# SIM800C_V1_2.net
KiCad netlist of a schematic drawn in Altium Designer
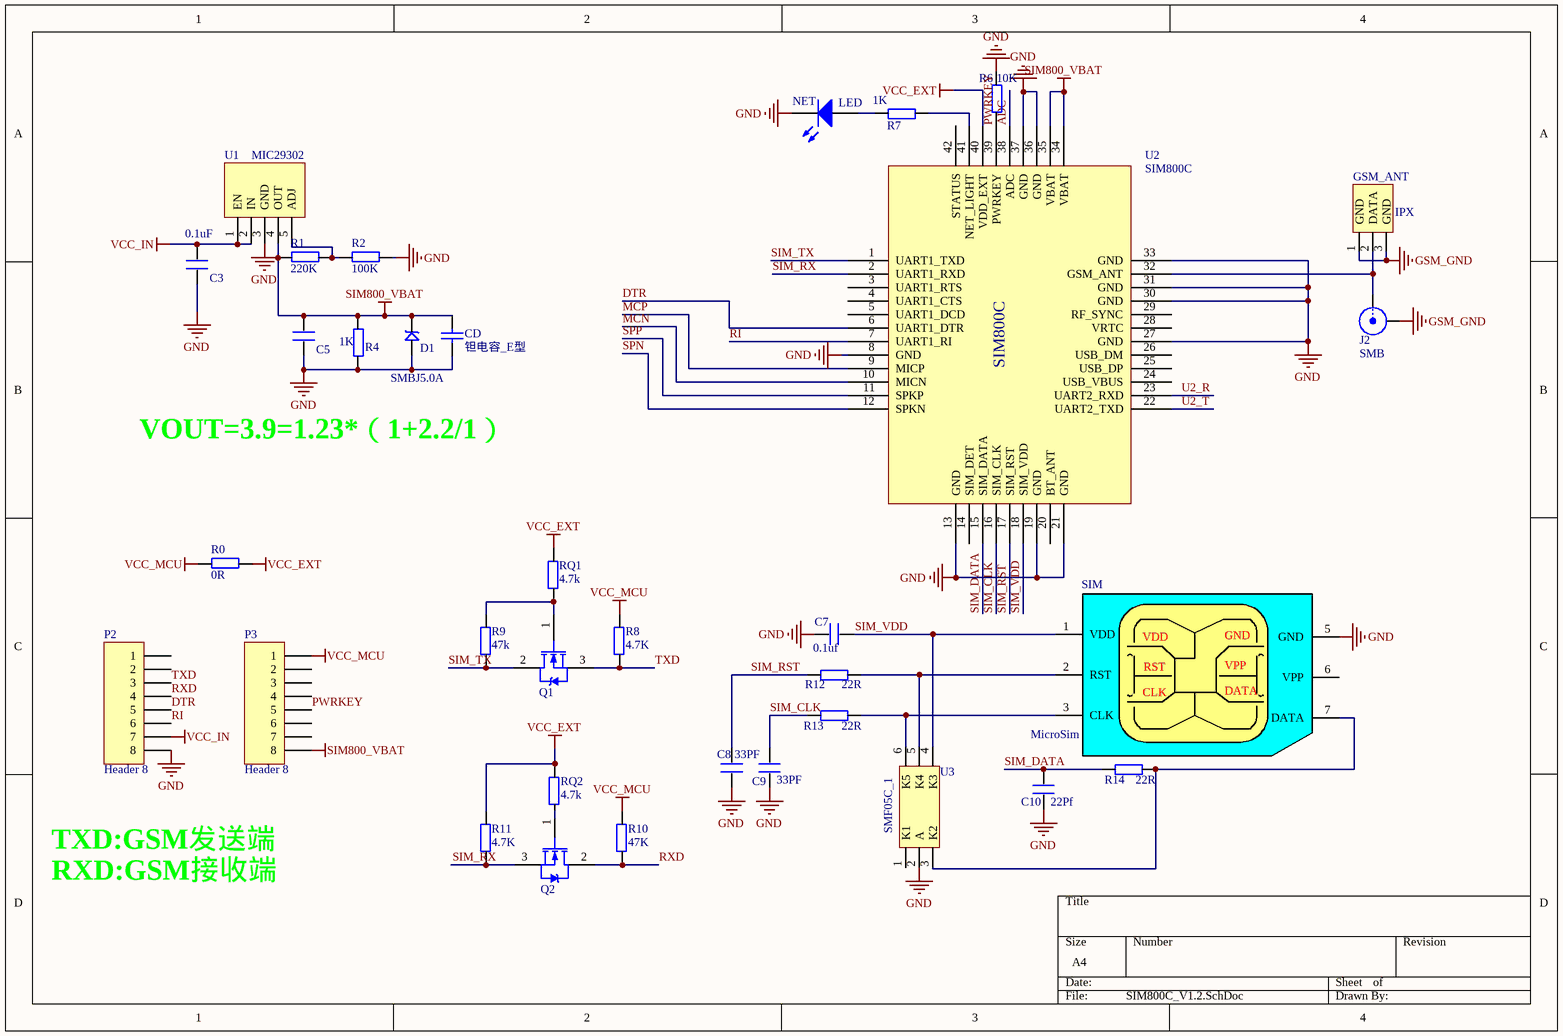
[diagram p0: SIM800C_V1.2.SchDoc]

(export (version "E")
  (design (tool "Eeschema 10.0.6"))
  (components
    (comp (ref "C3") (value "0.1uF") (footprint "0603P") (libsource (lib "SIM800C 原理图库") (part "C")))
    (comp (ref "C5") (value "0.1uF") (footprint "0603P") (libsource (lib "SIM800C 原理图库") (part "C_2")))
    (comp (ref "C7") (value "0.1uf") (footprint "0603P") (libsource (lib "SIM800C 原理图库") (part "C")))
    (comp (ref "C8")
      (value "22UF")
      (footprint "0603P")
      (fields (field (name "ALTIUM_UNNAMED_1") "33PF"))
      (libsource (lib "SIM800C 原理图库") (part "C"))
    )
    (comp (ref "C9")
      (value "22UF")
      (footprint "0603P")
      (fields (field (name "ALTIUM_UNNAMED_1") "33PF"))
      (libsource (lib "SIM800C 原理图库") (part "C"))
    )
    (comp (ref "C10") (value "22Pf") (footprint "0603P") (libsource (lib "SIM800C 原理图库") (part "C")))
    (comp (ref "CD") (value "钽电容_E型") (footprint "钽电容_E型") (libsource (lib "pvbox-lib") (part "钽电容_E型")))
    (comp (ref "D1")
      (value "SMBJ5.0A")
      (footprint "SMBJ")
      (description "TVS")
      (fields (field (name "ALTIUM_UNNAMED_1") "SMBJ5.0A"))
      (libsource (lib "SIM800C 原理图库") (part "SMBJ"))
    )
    (comp (ref "GSM_ANT")
      (value "IPX")
      (footprint "IPX")
      (description "IPEX座")
      (libsource (lib "SIM800C 原理图库") (part "IPEX"))
    )
    (comp (ref "J2")
      (value "SMB")
      (footprint "SMB_V-RJ45")
      (description "SMB Straight Connector")
      (fields (field (name "PUBLISHER") "Altium Limited"))
      (libsource (lib "SIM800C 原理图库") (part "SMB"))
    )
    (comp (ref "NET")
      (value "LED")
      (footprint "SMDLED")
      (description "Typical RED, GREEN, YELLOW, AMBER GaAs LED")
      (fields (field (name "PUBLISHER") "Altium Limited"))
      (libsource (lib "SIM800C 原理图库") (part "LED2"))
    )
    (comp (ref "P2")
      (value "Header 8")
      (footprint "HDR1X8")
      (description "Header, 8-Pin")
      (fields (field (name "PUBLISHER") "Altium Limited"))
      (libsource (lib "SIM800C 原理图库") (part "Header 8"))
    )
    (comp (ref "P3")
      (value "Header 8")
      (footprint "HDR1X8")
      (description "Header, 8-Pin")
      (fields (field (name "PUBLISHER") "Altium Limited"))
      (libsource (lib "SIM800C 原理图库") (part "Header 8"))
    )
    (comp (ref "Q1")
      (value "NMOS-2")
      (footprint "SOT-23")
      (description "N-Channel Power MOSFET")
      (fields (field (name "PUBLISHER") "Altium Limited"))
      (libsource (lib "SIM800C 原理图库") (part "NMOS-2"))
    )
    (comp (ref "Q2")
      (value "NMOS-2")
      (footprint "SOT-23")
      (description "N-Channel Power MOSFET")
      (fields (field (name "PUBLISHER") "Altium Limited"))
      (libsource (lib "SIM800C 原理图库") (part "NMOS-2"))
    )
    (comp (ref "R0") (value "0R") (footprint "0603P") (libsource (lib "SIM800C 原理图库") (part "R")))
    (comp (ref "R1") (value "220K") (footprint "0603P") (libsource (lib "SIM800C 原理图库") (part "R")))
    (comp (ref "R2") (value "100K") (footprint "0603P") (libsource (lib "SIM800C 原理图库") (part "R")))
    (comp (ref "R4") (value "1K") (footprint "0603P") (libsource (lib "SIM800C 原理图库") (part "R")))
    (comp (ref "R6") (value "10K") (footprint "CORE:0603P") (libsource (lib "SIM800C 原理图库") (part "R")))
    (comp (ref "R7") (value "1K") (footprint "CORE:0603P") (libsource (lib "SIM800C 原理图库") (part "R")))
    (comp (ref "R8") (value "4.7K") (footprint "CORE:0603P") (libsource (lib "SIM800C 原理图库") (part "R")))
    (comp (ref "R9") (value "47k") (footprint "CORE:0603P") (libsource (lib "SIM800C 原理图库") (part "R")))
    (comp (ref "R10") (value "47K") (footprint "CORE:0603P") (libsource (lib "SIM800C 原理图库") (part "R")))
    (comp (ref "R11") (value "4.7K") (footprint "CORE:0603P") (libsource (lib "SIM800C 原理图库") (part "R")))
    (comp (ref "R12") (value "22R") (footprint "CORE:0603P") (libsource (lib "SIM800C 原理图库") (part "R")))
    (comp (ref "R13") (value "22R") (footprint "CORE:0603P") (libsource (lib "SIM800C 原理图库") (part "R")))
    (comp (ref "R14") (value "22R") (footprint "CORE:0603P") (libsource (lib "SIM800C 原理图库") (part "R")))
    (comp (ref "RQ1") (value "4.7k") (footprint "CORE:0603P") (libsource (lib "SIM800C 原理图库") (part "R")))
    (comp (ref "RQ2") (value "4.7k") (footprint "CORE:0603P") (libsource (lib "SIM800C 原理图库") (part "R")))
    (comp (ref "SIM") (value "MicroSim") (footprint "SIM卡 自弹") (libsource (lib "pvbox-lib") (part "SIM卡 自弹")))
    (comp (ref "U1")
      (value "MIC29302")
      (footprint "D2PAK")
      (libsource (lib "SIM800C 原理图库") (part "MIC29302"))
    )
    (comp (ref "U2")
      (value "SIM800C")
      (footprint "SIM800C")
      (libsource (lib "SIM800C 原理图库") (part "SIM800C"))
    )
    (comp (ref "U3")
      (value "SMF05C_1")
      (footprint "SOT-363")
      (description "TVS")
      (libsource (lib "SIM800C 原理图库") (part "SMF05C_1"))
    )
  )
  (nets
    (net (code "1") (name "/ADC") (class "Default")
      (node (ref "U2") (pin "38") (pinfunction "ADC_38") (pintype "passive"))
    )
    (net (code "2") (name "/DTR") (class "Default")
      (node (ref "P2") (pin "5") (pinfunction "5_5") (pintype "passive"))
      (node (ref "U2") (pin "6") (pinfunction "UART1_DTR_6") (pintype "passive"))
    )
    (net (code "3") (name "/MCN") (class "Default")
      (node (ref "U2") (pin "10") (pinfunction "MICN_10") (pintype "passive"))
    )
    (net (code "4") (name "/MCP") (class "Default")
      (node (ref "U2") (pin "9") (pinfunction "MICP_9") (pintype "passive"))
    )
    (net (code "5") (name "/PWRKEY") (class "Default")
      (node (ref "P3") (pin "5") (pinfunction "5_5") (pintype "passive"))
      (node (ref "R6") (pin "1") (pintype "passive"))
      (node (ref "U2") (pin "39") (pinfunction "PWRKEY_39") (pintype "passive"))
    )
    (net (code "6") (name "/RI") (class "Default")
      (node (ref "P2") (pin "6") (pinfunction "6_6") (pintype "passive"))
      (node (ref "U2") (pin "7") (pinfunction "UART1_RI_7") (pintype "passive"))
    )
    (net (code "7") (name "/RXD") (class "Default")
      (node (ref "P2") (pin "4") (pinfunction "4_4") (pintype "passive"))
      (node (ref "Q2") (pin "2") (pinfunction "D_2") (pintype "passive"))
      (node (ref "R10") (pin "1") (pintype "passive"))
    )
    (net (code "8") (name "/SIM_CLK") (class "Default")
      (node (ref "C9") (pin "2") (pintype "passive"))
      (node (ref "R13") (pin "1") (pintype "passive"))
      (node (ref "U2") (pin "16") (pinfunction "SIM_CLK_16") (pintype "passive"))
    )
    (net (code "9") (name "/SIM_DATA") (class "Default")
      (node (ref "C10") (pin "2") (pintype "passive"))
      (node (ref "R14") (pin "1") (pintype "passive"))
      (node (ref "U2") (pin "15") (pinfunction "SIM_DATA_15") (pintype "passive"))
    )
    (net (code "10") (name "/SIM_RST") (class "Default")
      (node (ref "C8") (pin "2") (pintype "passive"))
      (node (ref "R12") (pin "1") (pintype "passive"))
      (node (ref "U2") (pin "17") (pinfunction "SIM_RST_17") (pintype "passive"))
    )
    (net (code "11") (name "/SIM_RX") (class "Default")
      (node (ref "Q2") (pin "3") (pinfunction "S_3") (pintype "passive"))
      (node (ref "R11") (pin "1") (pintype "passive"))
      (node (ref "U2") (pin "2") (pinfunction "UART1_RXD_2") (pintype "passive"))
    )
    (net (code "12") (name "/SIM_TX") (class "Default")
      (node (ref "Q1") (pin "2") (pinfunction "D_2") (pintype "passive"))
      (node (ref "R9") (pin "1") (pintype "passive"))
      (node (ref "U2") (pin "1") (pinfunction "UART1_TXD_1") (pintype "passive"))
    )
    (net (code "13") (name "/SIM_VDD") (class "Default")
      (node (ref "C7") (pin "2") (pintype "passive"))
      (node (ref "SIM") (pin "1") (pinfunction "VDD_1") (pintype "passive"))
      (node (ref "U2") (pin "18") (pinfunction "SIM_VDD_18") (pintype "passive"))
      (node (ref "U3") (pin "4") (pinfunction "K3_4") (pintype "passive"))
    )
    (net (code "14") (name "/SPN") (class "Default")
      (node (ref "U2") (pin "12") (pinfunction "SPKN_12") (pintype "passive"))
    )
    (net (code "15") (name "/SPP") (class "Default")
      (node (ref "U2") (pin "11") (pinfunction "SPKP_11") (pintype "passive"))
    )
    (net (code "16") (name "/TXD") (class "Default")
      (node (ref "P2") (pin "3") (pinfunction "3_3") (pintype "passive"))
      (node (ref "Q1") (pin "3") (pinfunction "S_3") (pintype "passive"))
      (node (ref "R8") (pin "1") (pintype "passive"))
    )
    (net (code "17") (name "/U2_R") (class "Default")
      (node (ref "U2") (pin "23") (pinfunction "UART2_RXD_23") (pintype "passive"))
    )
    (net (code "18") (name "/U2_T") (class "Default")
      (node (ref "U2") (pin "22") (pinfunction "UART2_TXD_22") (pintype "passive"))
    )
    (net (code "19") (name "GND") (class "Default")
      (node (ref "C10") (pin "1") (pintype "passive"))
      (node (ref "C3") (pin "1") (pintype "passive"))
      (node (ref "C5") (pin "2") (pintype "passive"))
      (node (ref "C7") (pin "1") (pintype "passive"))
      (node (ref "C8") (pin "1") (pintype "passive"))
      (node (ref "C9") (pin "1") (pintype "passive"))
      (node (ref "CD") (pin "1") (pinfunction "1_1") (pintype "passive"))
      (node (ref "D1") (pin "1") (pintype "passive"))
      (node (ref "NET") (pin "2") (pinfunction "K_2") (pintype "passive"))
      (node (ref "P2") (pin "8") (pinfunction "8_8") (pintype "passive"))
      (node (ref "R2") (pin "1") (pintype "passive"))
      (node (ref "R4") (pin "1") (pintype "passive"))
      (node (ref "R6") (pin "2") (pintype "passive"))
      (node (ref "SIM") (pin "5") (pinfunction "GND_5") (pintype "passive"))
      (node (ref "U1") (pin "3") (pinfunction "GND_3") (pintype "passive"))
      (node (ref "U2") (pin "13") (pinfunction "GND_13") (pintype "passive"))
      (node (ref "U2") (pin "19") (pinfunction "GND_19") (pintype "passive"))
      (node (ref "U2") (pin "21") (pinfunction "GND_21") (pintype "passive"))
      (node (ref "U2") (pin "27") (pinfunction "GND_27") (pintype "passive"))
      (node (ref "U2") (pin "30") (pinfunction "GND_30") (pintype "passive"))
      (node (ref "U2") (pin "31") (pinfunction "GND_31") (pintype "passive"))
      (node (ref "U2") (pin "33") (pinfunction "GND_33") (pintype "passive"))
      (node (ref "U2") (pin "36") (pinfunction "GND_36") (pintype "passive"))
      (node (ref "U2") (pin "37") (pinfunction "GND_37") (pintype "passive"))
      (node (ref "U2") (pin "8") (pinfunction "GND_8") (pintype "passive"))
      (node (ref "U3") (pin "2") (pinfunction "A_2") (pintype "passive"))
    )
    (net (code "20") (name "GSM_GND") (class "Default")
      (node (ref "GSM_ANT") (pin "1") (pinfunction "GND_1") (pintype "passive"))
      (node (ref "GSM_ANT") (pin "3") (pinfunction "GND_3") (pintype "passive"))
      (node (ref "J2") (pin "2") (pinfunction "Y_2") (pintype "passive"))
    )
    (net (code "21") (name "Net-(GSM_ANT-DATA)") (class "Default")
      (node (ref "GSM_ANT") (pin "2") (pinfunction "DATA_2") (pintype "passive"))
      (node (ref "J2") (pin "1") (pinfunction "X_1") (pintype "passive"))
      (node (ref "U2") (pin "32") (pinfunction "GSM_ANT_32") (pintype "passive"))
    )
    (net (code "22") (name "Net-(NET-A)") (class "Default")
      (node (ref "NET") (pin "1") (pinfunction "A_1") (pintype "passive"))
      (node (ref "R7") (pin "1") (pintype "passive"))
    )
    (net (code "23") (name "Net-(Q1-G)") (class "Default")
      (node (ref "Q1") (pin "1") (pinfunction "G_1") (pintype "passive"))
      (node (ref "R9") (pin "2") (pintype "passive"))
      (node (ref "RQ1") (pin "1") (pintype "passive"))
    )
    (net (code "24") (name "Net-(Q2-G)") (class "Default")
      (node (ref "Q2") (pin "1") (pinfunction "G_1") (pintype "passive"))
      (node (ref "RQ2") (pin "1") (pintype "passive"))
    )
    (net (code "25") (name "Net-(SIM-CLK)") (class "Default")
      (node (ref "R13") (pin "2") (pintype "passive"))
      (node (ref "SIM") (pin "3") (pinfunction "CLK_3") (pintype "passive"))
      (node (ref "U3") (pin "6") (pinfunction "K5_6") (pintype "passive"))
    )
    (net (code "26") (name "Net-(SIM-DATA)") (class "Default")
      (node (ref "R14") (pin "2") (pintype "passive"))
      (node (ref "SIM") (pin "7") (pinfunction "DATA_7") (pintype "passive"))
      (node (ref "U3") (pin "3") (pinfunction "K2_3") (pintype "passive"))
    )
    (net (code "27") (name "Net-(SIM-RST)") (class "Default")
      (node (ref "R12") (pin "2") (pintype "passive"))
      (node (ref "SIM") (pin "2") (pinfunction "RST_2") (pintype "passive"))
      (node (ref "U3") (pin "5") (pinfunction "K4_5") (pintype "passive"))
    )
    (net (code "28") (name "Net-(U1-ADJ)") (class "Default")
      (node (ref "R1") (pin "1") (pintype "passive"))
      (node (ref "R2") (pin "2") (pintype "passive"))
      (node (ref "U1") (pin "5") (pinfunction "ADJ_5") (pintype "passive"))
    )
    (net (code "29") (name "Net-(U2-NET_LIGHT)") (class "Default")
      (node (ref "R7") (pin "2") (pintype "passive"))
      (node (ref "U2") (pin "41") (pinfunction "NET_LIGHT_41") (pintype "passive"))
    )
    (net (code "30") (name "SIM800_VBAT") (class "Default")
      (node (ref "C5") (pin "1") (pintype "passive"))
      (node (ref "CD") (pin "2") (pinfunction "2_2") (pintype "passive"))
      (node (ref "D1") (pin "2") (pintype "passive"))
      (node (ref "P3") (pin "8") (pinfunction "8_8") (pintype "passive"))
      (node (ref "R1") (pin "2") (pintype "passive"))
      (node (ref "R4") (pin "2") (pintype "passive"))
      (node (ref "U1") (pin "4") (pinfunction "OUT_4") (pintype "passive"))
      (node (ref "U2") (pin "34") (pinfunction "VBAT_34") (pintype "passive"))
      (node (ref "U2") (pin "35") (pinfunction "VBAT_35") (pintype "passive"))
    )
    (net (code "31") (name "VCC_EXT") (class "Default")
      (node (ref "R0") (pin "1") (pintype "passive"))
      (node (ref "R11") (pin "2") (pintype "passive"))
      (node (ref "RQ1") (pin "2") (pintype "passive"))
      (node (ref "RQ2") (pin "2") (pintype "passive"))
      (node (ref "U2") (pin "40") (pinfunction "VDD_EXT_40") (pintype "passive"))
    )
    (net (code "32") (name "VCC_IN") (class "Default")
      (node (ref "C3") (pin "2") (pintype "passive"))
      (node (ref "P2") (pin "7") (pinfunction "7_7") (pintype "passive"))
      (node (ref "U1") (pin "1") (pinfunction "EN_1") (pintype "passive"))
      (node (ref "U1") (pin "2") (pinfunction "IN_2") (pintype "passive"))
    )
    (net (code "33") (name "VCC_MCU") (class "Default")
      (node (ref "P3") (pin "1") (pinfunction "1_1") (pintype "passive"))
      (node (ref "R0") (pin "2") (pintype "passive"))
      (node (ref "R10") (pin "2") (pintype "passive"))
      (node (ref "R8") (pin "2") (pintype "passive"))
    )
    (net (code "34") (name "unconnected-(P2-Pad1)") (class "Default")
      (node (ref "P2") (pin "1") (pinfunction "1_1") (pintype "passive"))
    )
    (net (code "35") (name "unconnected-(P2-Pad2)") (class "Default")
      (node (ref "P2") (pin "2") (pinfunction "2_2") (pintype "passive"))
    )
    (net (code "36") (name "unconnected-(P3-Pad2)") (class "Default")
      (node (ref "P3") (pin "2") (pinfunction "2_2") (pintype "passive"))
    )
    (net (code "37") (name "unconnected-(P3-Pad3)") (class "Default")
      (node (ref "P3") (pin "3") (pinfunction "3_3") (pintype "passive"))
    )
    (net (code "38") (name "unconnected-(P3-Pad4)") (class "Default")
      (node (ref "P3") (pin "4") (pinfunction "4_4") (pintype "passive"))
    )
    (net (code "39") (name "unconnected-(P3-Pad6)") (class "Default")
      (node (ref "P3") (pin "6") (pinfunction "6_6") (pintype "passive"))
    )
    (net (code "40") (name "unconnected-(P3-Pad7)") (class "Default")
      (node (ref "P3") (pin "7") (pinfunction "7_7") (pintype "passive"))
    )
    (net (code "41") (name "unconnected-(SIM-VPP-Pad6)") (class "Default")
      (node (ref "SIM") (pin "6") (pinfunction "VPP_6") (pintype "passive"))
    )
    (net (code "42") (name "unconnected-(U2-BT_ANT-Pad20)") (class "Default")
      (node (ref "U2") (pin "20") (pinfunction "BT_ANT_20") (pintype "passive"))
    )
    (net (code "43") (name "unconnected-(U2-RF_SYNC-Pad29)") (class "Default")
      (node (ref "U2") (pin "29") (pinfunction "RF_SYNC_29") (pintype "passive"))
    )
    (net (code "44") (name "unconnected-(U2-SIM_DET-Pad14)") (class "Default")
      (node (ref "U2") (pin "14") (pinfunction "SIM_DET_14") (pintype "passive"))
    )
    (net (code "45") (name "unconnected-(U2-STATUS-Pad42)") (class "Default")
      (node (ref "U2") (pin "42") (pinfunction "STATUS_42") (pintype "passive"))
    )
    (net (code "46") (name "unconnected-(U2-UART1_CTS-Pad4)") (class "Default")
      (node (ref "U2") (pin "4") (pinfunction "UART1_CTS_4") (pintype "passive"))
    )
    (net (code "47") (name "unconnected-(U2-UART1_DCD-Pad5)") (class "Default")
      (node (ref "U2") (pin "5") (pinfunction "UART1_DCD_5") (pintype "passive"))
    )
    (net (code "48") (name "unconnected-(U2-UART1_RTS-Pad3)") (class "Default")
      (node (ref "U2") (pin "3") (pinfunction "UART1_RTS_3") (pintype "passive"))
    )
    (net (code "49") (name "unconnected-(U2-USB_DM-Pad26)") (class "Default")
      (node (ref "U2") (pin "26") (pinfunction "USB_DM_26") (pintype "passive"))
    )
    (net (code "50") (name "unconnected-(U2-USB_DP-Pad25)") (class "Default")
      (node (ref "U2") (pin "25") (pinfunction "USB_DP_25") (pintype "passive"))
    )
    (net (code "51") (name "unconnected-(U2-USB_VBUS-Pad24)") (class "Default")
      (node (ref "U2") (pin "24") (pinfunction "USB_VBUS_24") (pintype "passive"))
    )
    (net (code "52") (name "unconnected-(U2-VRTC-Pad28)") (class "Default")
      (node (ref "U2") (pin "28") (pinfunction "VRTC_28") (pintype "passive"))
    )
    (net (code "53") (name "unconnected-(U3-K1-Pad1)") (class "Default")
      (node (ref "U3") (pin "1") (pinfunction "K1_1") (pintype "passive"))
    )
  )
)
